# SPW2430-Silicon-Mic_Rev-B.net
KiCad netlist of a schematic drawn in EAGLE
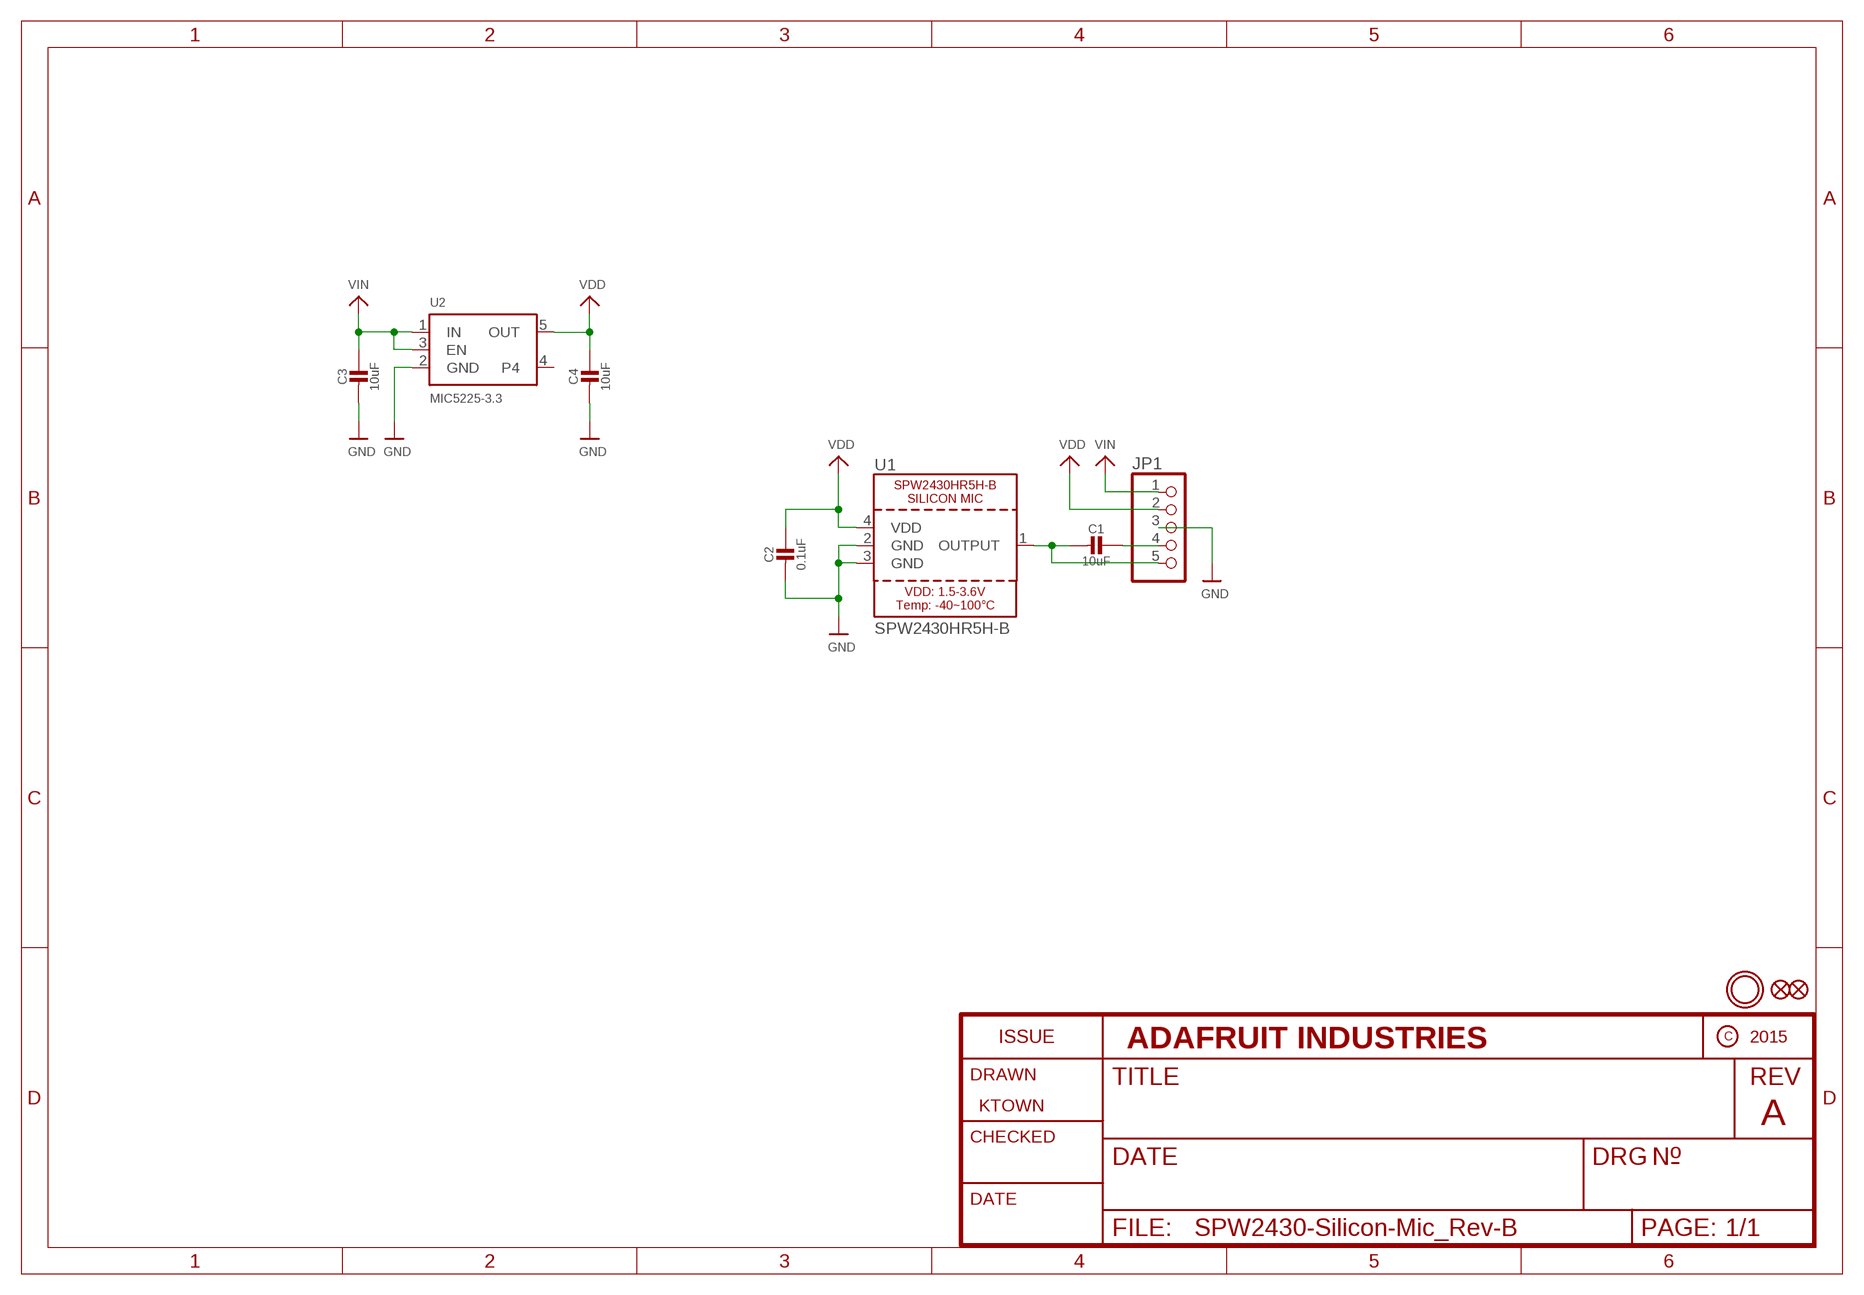
[diagram p0: schematic, sheet 1]

(export (version "E")
  (design (tool "Eeschema 10.0.6"))
  (components
    (comp (ref "C1")
      (value "10uF")
      (footprint "eagle-import:0805-NO")
      (libsource (lib "eagle-import") (part "CAP_CERAMIC0805-NOOUTLINE"))
    )
    (comp (ref "C2")
      (value "0.1uF")
      (footprint "eagle-import:0805-NO")
      (libsource (lib "eagle-import") (part "CAP_CERAMIC0805-NOOUTLINE"))
    )
    (comp (ref "C3")
      (value "10uF")
      (footprint "eagle-import:0805-NO")
      (libsource (lib "eagle-import") (part "CAP_CERAMIC0805-NOOUTLINE"))
    )
    (comp (ref "C4")
      (value "10uF")
      (footprint "eagle-import:0805-NO")
      (libsource (lib "eagle-import") (part "CAP_CERAMIC0805-NOOUTLINE"))
    )
    (comp (ref "FID1")
      (value "FIDUCIAL\"\"")
      (footprint "eagle-import:FIDUCIAL_1MM")
      (libsource (lib "eagle-import") (part "FIDUCIAL{dblquote}{dblquote}"))
    )
    (comp (ref "FID2")
      (value "FIDUCIAL\"\"")
      (footprint "eagle-import:FIDUCIAL_1MM")
      (libsource (lib "eagle-import") (part "FIDUCIAL{dblquote}{dblquote}"))
    )
    (comp (ref "JP1")
      (value "HEADER-1X576MIL")
      (footprint "eagle-import:1X05_ROUND_76")
      (libsource (lib "eagle-import") (part "HEADER-1X576MIL"))
    )
    (comp (ref "U$12")
      (value "MOUNTINGHOLE2.5")
      (footprint "eagle-import:MOUNTINGHOLE_2.5_PLATED")
      (libsource (lib "eagle-import") (part "MOUNTINGHOLE2.5"))
    )
    (comp (ref "U1")
      (value "SPW2430HR5H-B")
      (footprint "eagle-import:SPW2430HR5H-B")
      (libsource (lib "eagle-import") (part "SPW2430HR5H-B"))
    )
    (comp (ref "U2")
      (value "MIC5225-3.3")
      (footprint "eagle-import:SOT23-5")
      (libsource (lib "eagle-import") (part "VREG_SOT23-5"))
    )
  )
  (nets
    (net (code "1") (name "GND") (class "Default")
      (node (ref "C2") (pin "2") (pinfunction "2_2") (pintype "passive"))
      (node (ref "C3") (pin "2") (pinfunction "2_2") (pintype "passive"))
      (node (ref "C4") (pin "2") (pinfunction "2_2") (pintype "passive"))
      (node (ref "JP1") (pin "3") (pinfunction "3_3") (pintype "passive"))
      (node (ref "U1") (pin "2") (pinfunction "GND_2") (pintype "power_in"))
      (node (ref "U1") (pin "3") (pinfunction "GND_3") (pintype "power_in"))
      (node (ref "U2") (pin "2") (pinfunction "GND_2") (pintype "power_in"))
    )
    (net (code "2") (name "Net-(C1-Pad1)") (class "Default")
      (node (ref "C1") (pin "1") (pinfunction "1_1") (pintype "passive"))
      (node (ref "JP1") (pin "4") (pinfunction "4_4") (pintype "passive"))
    )
    (net (code "3") (name "Net-(U1-OUTPUT)") (class "Default")
      (node (ref "C1") (pin "2") (pinfunction "2_2") (pintype "passive"))
      (node (ref "JP1") (pin "5") (pinfunction "5_5") (pintype "passive"))
      (node (ref "U1") (pin "1") (pinfunction "OUTPUT_1") (pintype "output"))
    )
    (net (code "4") (name "VDD") (class "Default")
      (node (ref "C2") (pin "1") (pinfunction "1_1") (pintype "passive"))
      (node (ref "C4") (pin "1") (pinfunction "1_1") (pintype "passive"))
      (node (ref "JP1") (pin "2") (pinfunction "2_2") (pintype "passive"))
      (node (ref "U1") (pin "4") (pinfunction "VDD_4") (pintype "power_in"))
      (node (ref "U2") (pin "5") (pinfunction "OUT_5") (pintype "power_in"))
    )
    (net (code "5") (name "VIN") (class "Default")
      (node (ref "C3") (pin "1") (pinfunction "1_1") (pintype "passive"))
      (node (ref "JP1") (pin "1") (pinfunction "1_1") (pintype "passive"))
      (node (ref "U2") (pin "1") (pinfunction "IN_1") (pintype "power_in"))
      (node (ref "U2") (pin "3") (pinfunction "EN_3") (pintype "input"))
    )
    (net (code "6") (name "unconnected-(U2-P4-Pad4)") (class "Default")
      (node (ref "U2") (pin "4") (pinfunction "P4_4") (pintype "bidirectional"))
    )
  )
)
